# ledpar56.net
KiCad netlist of a schematic drawn in EAGLE
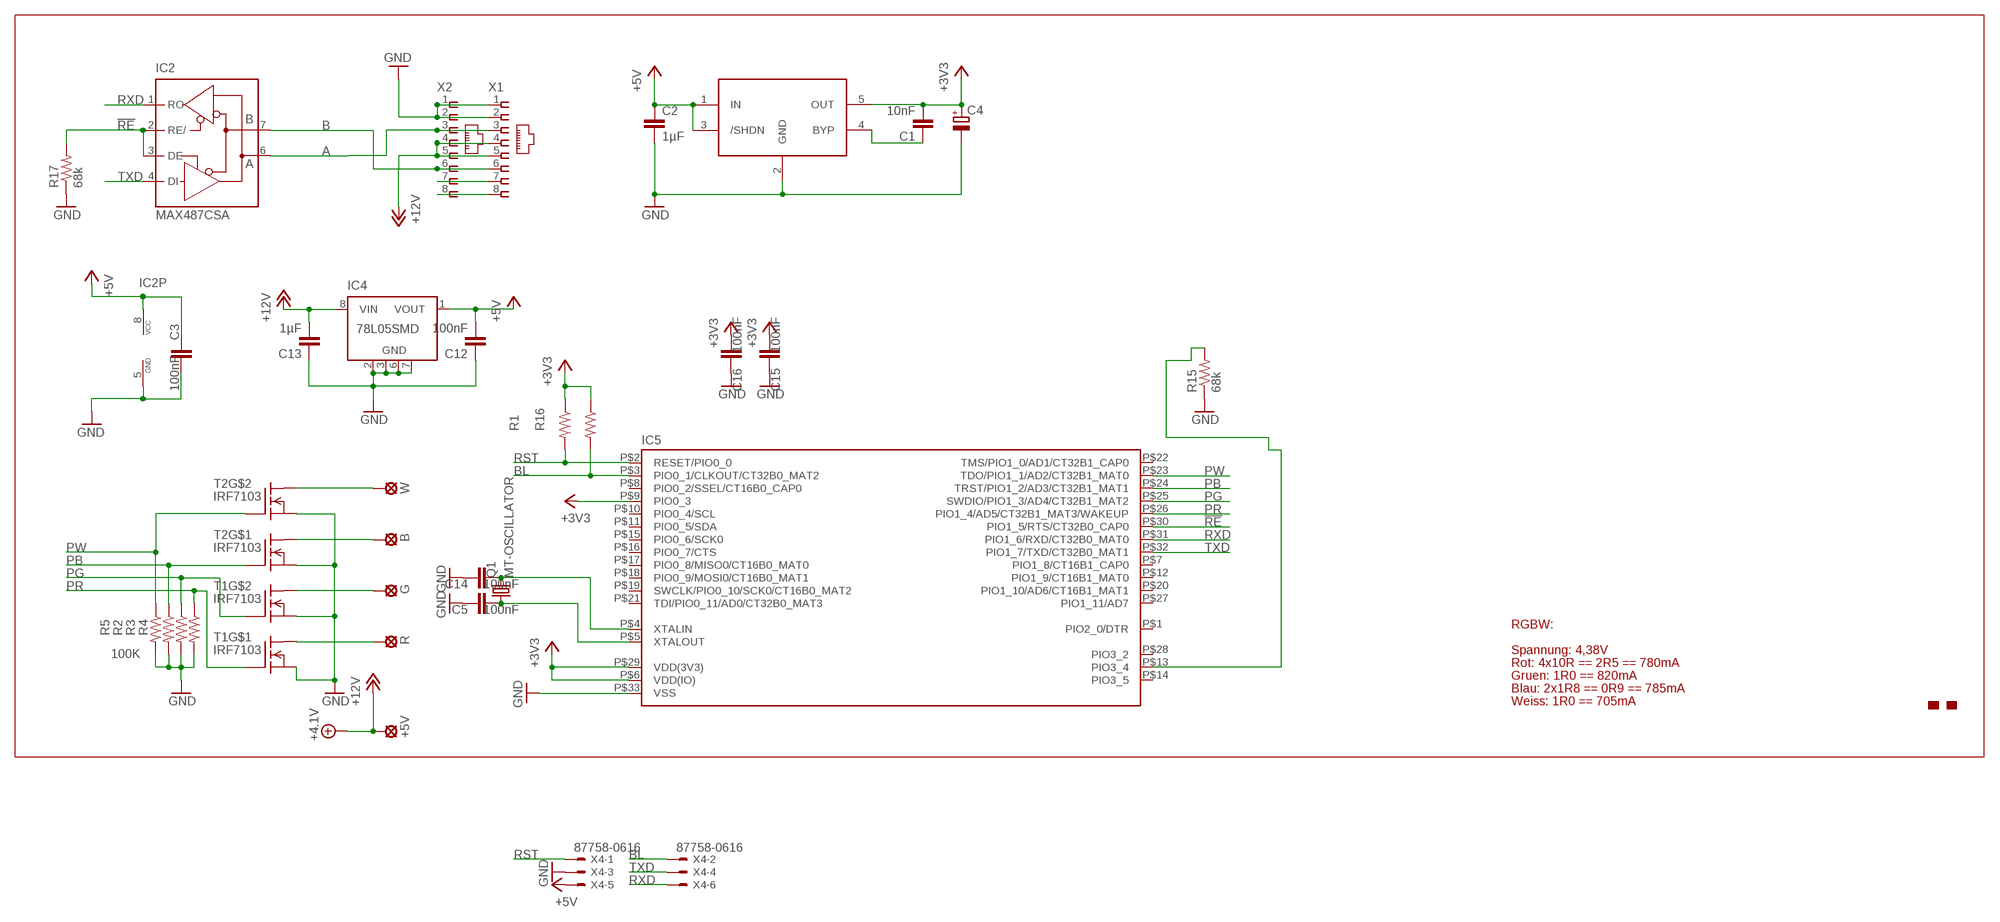
[diagram p0: schematic, sheet 1]

(export (version "E")
  (design (tool "Eeschema 10.0.6"))
  (components
    (comp (ref "+5V")
      (value "SE14")
      (footprint "eagle-import:SE14")
      (libsource (lib "eagle-import") (part "SE14"))
    )
    (comp (ref "B")
      (value "SE14")
      (footprint "eagle-import:SE14")
      (libsource (lib "eagle-import") (part "SE14"))
    )
    (comp (ref "C1")
      (value "10nF")
      (footprint "eagle-import:C0402")
      (libsource (lib "eagle-import") (part "C-EUC0402"))
    )
    (comp (ref "C2")
      (value "1µF")
      (footprint "eagle-import:0805")
      (libsource (lib "eagle-import") (part "SparkFun-Capacitors_CAP0805"))
    )
    (comp (ref "C3")
      (value "100nF")
      (footprint "eagle-import:0402-CAP")
      (libsource (lib "eagle-import") (part "CAP0402-CAP"))
    )
    (comp (ref "C4")
      (value "CPOL-EUSMCA")
      (footprint "eagle-import:SMC_A")
      (libsource (lib "eagle-import") (part "CPOL-EUSMCA"))
    )
    (comp (ref "C5")
      (value "100nF")
      (footprint "eagle-import:0402-CAP")
      (libsource (lib "eagle-import") (part "CAP0402-CAP"))
    )
    (comp (ref "C12")
      (value "100nF")
      (footprint "eagle-import:0402-CAP")
      (libsource (lib "eagle-import") (part "CAP0402-CAP"))
    )
    (comp (ref "C13")
      (value "1µF")
      (footprint "eagle-import:0805")
      (libsource (lib "eagle-import") (part "CAP0805"))
    )
    (comp (ref "C14")
      (value "100nF")
      (footprint "eagle-import:0402-CAP")
      (libsource (lib "eagle-import") (part "CAP0402-CAP"))
    )
    (comp (ref "C15")
      (value "100nF")
      (footprint "eagle-import:0402-CAP")
      (libsource (lib "eagle-import") (part "CAP0402-CAP"))
    )
    (comp (ref "C16")
      (value "100nF")
      (footprint "eagle-import:0402-CAP")
      (libsource (lib "eagle-import") (part "CAP0402-CAP"))
    )
    (comp (ref "G")
      (value "SE14")
      (footprint "eagle-import:SE14")
      (libsource (lib "eagle-import") (part "SE14"))
    )
    (comp (ref "IC1")
      (value "LT1761")
      (footprint "eagle-import:SOT23-5L")
      (libsource (lib "eagle-import") (part "LT1761"))
    )
    (comp (ref "IC2")
      (value "MAX487CSA")
      (footprint "eagle-import:SO08")
      (fields (field (name "MF") "MAXIM") (field (name "MPN") "MAX481CSA"))
      (libsource (lib "eagle-import") (part "MAX481CSA"))
    )
    (comp (ref "IC4")
      (value "78L05SMD")
      (footprint "eagle-import:SO08")
      (libsource (lib "eagle-import") (part "78LSMD05"))
    )
    (comp (ref "IC5")
      (value "LPC1113/4_QFN")
      (footprint "eagle-import:HVQFN33-7X7")
      (fields (field (name "MANF") "NXP"))
      (libsource (lib "eagle-import") (part "LPC1113/4_QFN"))
    )
    (comp (ref "Q1")
      (value "MT-OSCILLATOR")
      (footprint "eagle-import:MT")
      (libsource (lib "eagle-import") (part "MT-OSCILLATOR"))
    )
    (comp (ref "R")
      (value "SE14")
      (footprint "eagle-import:SE14")
      (libsource (lib "eagle-import") (part "SE14"))
    )
    (comp (ref "R1")
      (value "100K")
      (footprint "eagle-import:0402-RES")
      (libsource (lib "eagle-import") (part "RESISTOR0402-RES"))
    )
    (comp (ref "R2")
      (value "100K")
      (footprint "eagle-import:0402-RES")
      (libsource (lib "eagle-import") (part "RESISTOR0402-RES"))
    )
    (comp (ref "R3")
      (value "100K")
      (footprint "eagle-import:0402-RES")
      (libsource (lib "eagle-import") (part "RESISTOR0402-RES"))
    )
    (comp (ref "R4")
      (value "100K")
      (footprint "eagle-import:0402-RES")
      (libsource (lib "eagle-import") (part "RESISTOR0402-RES"))
    )
    (comp (ref "R5")
      (value "100K")
      (footprint "eagle-import:0402-RES")
      (libsource (lib "eagle-import") (part "RESISTOR0402-RES"))
    )
    (comp (ref "R15")
      (value "68k")
      (footprint "eagle-import:0402-RES")
      (libsource (lib "eagle-import") (part "RESISTOR0402-RES"))
    )
    (comp (ref "R16")
      (value "100K")
      (footprint "eagle-import:0402-RES")
      (libsource (lib "eagle-import") (part "RESISTOR0402-RES"))
    )
    (comp (ref "R17")
      (value "68k")
      (footprint "eagle-import:0402-RES")
      (libsource (lib "eagle-import") (part "RESISTOR0402-RES"))
    )
    (comp (ref "T1")
      (value "IRF7103")
      (footprint "eagle-import:SO-8")
      (libsource (lib "eagle-import") (part "IRF7103"))
    )
    (comp (ref "T2")
      (value "IRF7103")
      (footprint "eagle-import:SO-8")
      (libsource (lib "eagle-import") (part "IRF7103"))
    )
    (comp (ref "U$1")
      (value "MAKE-DD_LOGO'PROMPT'")
      (footprint "eagle-import:MAKE-DD_LOGO_PROMPT")
      (libsource (lib "eagle-import") (part "MAKE-DD_LOGO'PROMPT'"))
    )
    (comp (ref "W")
      (value "SE14")
      (footprint "eagle-import:SE14")
      (libsource (lib "eagle-import") (part "SE14"))
    )
    (comp (ref "X1")
      (value "RJ45-8L-B")
      (footprint "eagle-import:RJ45-NO-SHIELD")
      (fields (field (name "MF") "TYCO ELECTRONICS"))
      (libsource (lib "eagle-import") (part "RJ45-8L-B"))
    )
    (comp (ref "X2")
      (value "RJ45-8L-B")
      (footprint "eagle-import:RJ45-NO-SHIELD")
      (fields (field (name "MF") "TYCO ELECTRONICS"))
      (libsource (lib "eagle-import") (part "RJ45-8L-B"))
    )
    (comp (ref "X4")
      (value "87758-0616")
      (footprint "eagle-import:87758-0616")
      (libsource (lib "eagle-import") (part "87758-0616"))
    )
  )
  (nets
    (net (code "1") (name "+3V3") (class "Default")
      (node (ref "C1") (pin "2") (pinfunction "2_2") (pintype "passive"))
      (node (ref "C15") (pin "2") (pinfunction "2_2") (pintype "passive"))
      (node (ref "C16") (pin "2") (pinfunction "2_2") (pintype "passive"))
      (node (ref "C4") (pin "+") (pinfunction "+_+") (pintype "passive"))
      (node (ref "IC1") (pin "5") (pinfunction "OUT_5") (pintype "bidirectional"))
      (node (ref "IC5") (pin "P$29") (pinfunction "VDD(3V3)_P$29") (pintype "power_in"))
      (node (ref "IC5") (pin "P$6") (pinfunction "VDD(IO)_P$6") (pintype "power_in"))
      (node (ref "IC5") (pin "P$9") (pinfunction "PIO0_3_P$9") (pintype "bidirectional"))
      (node (ref "R1") (pin "1") (pinfunction "1_1") (pintype "passive"))
      (node (ref "R16") (pin "1") (pinfunction "1_1") (pintype "passive"))
    )
    (net (code "2") (name "+5V") (class "Default")
      (node (ref "C12") (pin "2") (pinfunction "2_2") (pintype "passive"))
      (node (ref "C2") (pin "1") (pinfunction "1_1") (pintype "passive"))
      (node (ref "C3") (pin "1") (pinfunction "1_1") (pintype "passive"))
      (node (ref "IC1") (pin "1") (pinfunction "IN_1") (pintype "bidirectional"))
      (node (ref "IC1") (pin "3") (pinfunction "/SHDN_3") (pintype "bidirectional"))
      (node (ref "IC2") (pin "8") (pinfunction "VCC_8") (pintype "power_in"))
      (node (ref "IC4") (pin "1") (pinfunction "VOUT_1") (pintype "output"))
      (node (ref "X4") (pin "5") (pinfunction "S_5") (pintype "passive"))
    )
    (net (code "3") (name "+12V") (class "Default")
      (node (ref "+5V") (pin "MP") (pinfunction "MP_MP") (pintype "passive"))
      (node (ref "C13") (pin "2") (pinfunction "2_2") (pintype "passive"))
      (node (ref "IC4") (pin "8") (pinfunction "VIN_8") (pintype "passive"))
      (node (ref "X1") (pin "4") (pinfunction "4_4") (pintype "passive"))
      (node (ref "X1") (pin "5") (pinfunction "5_5") (pintype "passive"))
      (node (ref "X2") (pin "4") (pinfunction "4_4") (pintype "passive"))
      (node (ref "X2") (pin "5") (pinfunction "5_5") (pintype "passive"))
    )
    (net (code "4") (name "/A") (class "Default")
      (node (ref "IC2") (pin "6") (pinfunction "A_6") (pintype "passive"))
      (node (ref "X1") (pin "3") (pinfunction "3_3") (pintype "passive"))
      (node (ref "X2") (pin "3") (pinfunction "3_3") (pintype "passive"))
    )
    (net (code "5") (name "/B") (class "Default")
      (node (ref "IC2") (pin "7") (pinfunction "B_7") (pintype "passive"))
      (node (ref "X1") (pin "6") (pinfunction "6_6") (pintype "passive"))
      (node (ref "X2") (pin "6") (pinfunction "6_6") (pintype "passive"))
    )
    (net (code "6") (name "/BL") (class "Default")
      (node (ref "IC5") (pin "P$3") (pinfunction "PIO0_1/CLKOUT/CT32B0_MAT2_P$3") (pintype "bidirectional"))
      (node (ref "R16") (pin "2") (pinfunction "2_2") (pintype "passive"))
      (node (ref "X4") (pin "2") (pinfunction "S_2") (pintype "passive"))
    )
    (net (code "7") (name "/PB") (class "Default")
      (node (ref "IC5") (pin "P$24") (pinfunction "TRST/PIO1_2/AD3/CT32B1_MAT1_P$24") (pintype "bidirectional"))
      (node (ref "R2") (pin "1") (pinfunction "1_1") (pintype "passive"))
      (node (ref "T2") (pin "2") (pinfunction "G_2") (pintype "passive"))
    )
    (net (code "8") (name "/PG") (class "Default")
      (node (ref "IC5") (pin "P$25") (pinfunction "SWDIO/PIO1_3/AD4/CT32B1_MAT2_P$25") (pintype "bidirectional"))
      (node (ref "R3") (pin "1") (pinfunction "1_1") (pintype "passive"))
      (node (ref "T1") (pin "4") (pinfunction "G_4") (pintype "passive"))
    )
    (net (code "9") (name "/PR") (class "Default")
      (node (ref "IC5") (pin "P$26") (pinfunction "PIO1_4/AD5/CT32B1_MAT3/WAKEUP_P$26") (pintype "bidirectional"))
      (node (ref "R4") (pin "1") (pinfunction "1_1") (pintype "passive"))
      (node (ref "T1") (pin "2") (pinfunction "G_2") (pintype "passive"))
    )
    (net (code "10") (name "/PW") (class "Default")
      (node (ref "IC5") (pin "P$23") (pinfunction "TDO/PIO1_1/AD2/CT32B1_MAT0_P$23") (pintype "bidirectional"))
      (node (ref "R5") (pin "1") (pinfunction "1_1") (pintype "passive"))
      (node (ref "T2") (pin "4") (pinfunction "G_4") (pintype "passive"))
    )
    (net (code "11") (name "/RST") (class "Default")
      (node (ref "IC5") (pin "P$2") (pinfunction "RESET/PIO0_0_P$2") (pintype "bidirectional"))
      (node (ref "R1") (pin "2") (pinfunction "2_2") (pintype "passive"))
      (node (ref "X4") (pin "1") (pinfunction "S_1") (pintype "passive"))
    )
    (net (code "12") (name "/RXD") (class "Default")
      (node (ref "IC2") (pin "1") (pinfunction "RO_1") (pintype "output"))
      (node (ref "IC5") (pin "P$31") (pinfunction "PIO1_6/RXD/CT32B0_MAT0_P$31") (pintype "bidirectional"))
      (node (ref "X4") (pin "6") (pinfunction "S_6") (pintype "passive"))
    )
    (net (code "13") (name "/TXD") (class "Default")
      (node (ref "IC2") (pin "4") (pinfunction "DI_4") (pintype "input"))
      (node (ref "IC5") (pin "P$32") (pinfunction "PIO1_7/TXD/CT32B0_MAT1_P$32") (pintype "bidirectional"))
      (node (ref "X4") (pin "4") (pinfunction "S_4") (pintype "passive"))
    )
    (net (code "14") (name "/~{RE}") (class "Default")
      (node (ref "IC2") (pin "2") (pinfunction "RE/_2") (pintype "input"))
      (node (ref "IC2") (pin "3") (pinfunction "DE_3") (pintype "input"))
      (node (ref "IC5") (pin "P$30") (pinfunction "PIO1_5/RTS/CT32B0_CAP0_P$30") (pintype "bidirectional"))
      (node (ref "R17") (pin "2") (pinfunction "2_2") (pintype "passive"))
    )
    (net (code "15") (name "GND") (class "Default")
      (node (ref "C12") (pin "1") (pinfunction "1_1") (pintype "passive"))
      (node (ref "C13") (pin "1") (pinfunction "1_1") (pintype "passive"))
      (node (ref "C14") (pin "1") (pinfunction "1_1") (pintype "passive"))
      (node (ref "C15") (pin "1") (pinfunction "1_1") (pintype "passive"))
      (node (ref "C16") (pin "1") (pinfunction "1_1") (pintype "passive"))
      (node (ref "C2") (pin "2") (pinfunction "2_2") (pintype "passive"))
      (node (ref "C3") (pin "2") (pinfunction "2_2") (pintype "passive"))
      (node (ref "C4") (pin "-") (pinfunction "-_-") (pintype "passive"))
      (node (ref "C5") (pin "1") (pinfunction "1_1") (pintype "passive"))
      (node (ref "IC1") (pin "2") (pinfunction "GND_2") (pintype "bidirectional"))
      (node (ref "IC2") (pin "5") (pinfunction "GND_5") (pintype "power_in"))
      (node (ref "IC4") (pin "2") (pinfunction "GND_2") (pintype "power_in"))
      (node (ref "IC4") (pin "3") (pinfunction "GND_3") (pintype "power_in"))
      (node (ref "IC4") (pin "6") (pinfunction "GND_6") (pintype "power_in"))
      (node (ref "IC4") (pin "7") (pinfunction "GND_7") (pintype "power_in"))
      (node (ref "IC5") (pin "P$33") (pinfunction "VSS_P$33") (pintype "power_in"))
      (node (ref "R15") (pin "1") (pinfunction "1_1") (pintype "passive"))
      (node (ref "R17") (pin "1") (pinfunction "1_1") (pintype "passive"))
      (node (ref "R2") (pin "2") (pinfunction "2_2") (pintype "passive"))
      (node (ref "R3") (pin "2") (pinfunction "2_2") (pintype "passive"))
      (node (ref "R4") (pin "2") (pinfunction "2_2") (pintype "passive"))
      (node (ref "R5") (pin "2") (pinfunction "2_2") (pintype "passive"))
      (node (ref "T1") (pin "1") (pinfunction "S_1") (pintype "passive"))
      (node (ref "T1") (pin "3") (pinfunction "S_3") (pintype "passive"))
      (node (ref "T2") (pin "1") (pinfunction "S_1") (pintype "passive"))
      (node (ref "T2") (pin "3") (pinfunction "S_3") (pintype "passive"))
      (node (ref "X1") (pin "1") (pinfunction "1_1") (pintype "passive"))
      (node (ref "X1") (pin "2") (pinfunction "2_2") (pintype "passive"))
      (node (ref "X2") (pin "1") (pinfunction "1_1") (pintype "passive"))
      (node (ref "X2") (pin "2") (pinfunction "2_2") (pintype "passive"))
      (node (ref "X4") (pin "3") (pinfunction "S_3") (pintype "passive"))
    )
    (net (code "16") (name "Net-(IC1-BYP)") (class "Default")
      (node (ref "C1") (pin "1") (pinfunction "1_1") (pintype "passive"))
      (node (ref "IC1") (pin "4") (pinfunction "BYP_4") (pintype "bidirectional"))
    )
    (net (code "17") (name "Net-(IC5-PIO3_4)") (class "Default")
      (node (ref "IC5") (pin "P$13") (pinfunction "PIO3_4_P$13") (pintype "bidirectional"))
      (node (ref "R15") (pin "2") (pinfunction "2_2") (pintype "passive"))
    )
    (net (code "18") (name "Net-(IC5-XTALIN)") (class "Default")
      (node (ref "C14") (pin "2") (pinfunction "2_2") (pintype "passive"))
      (node (ref "IC5") (pin "P$4") (pinfunction "XTALIN_P$4") (pintype "input"))
      (node (ref "Q1") (pin "3") (pinfunction "2_3") (pintype "passive"))
    )
    (net (code "19") (name "Net-(IC5-XTALOUT)") (class "Default")
      (node (ref "C5") (pin "2") (pinfunction "2_2") (pintype "passive"))
      (node (ref "IC5") (pin "P$5") (pinfunction "XTALOUT_P$5") (pintype "output"))
      (node (ref "Q1") (pin "1") (pinfunction "1_1") (pintype "passive"))
    )
    (net (code "20") (name "Net-(T1A-D1)") (class "Default")
      (node (ref "R") (pin "MP") (pinfunction "MP_MP") (pintype "passive"))
      (node (ref "T1") (pin "8") (pinfunction "D1_8") (pintype "passive"))
    )
    (net (code "21") (name "Net-(T1B-D1)") (class "Default")
      (node (ref "G") (pin "MP") (pinfunction "MP_MP") (pintype "passive"))
      (node (ref "T1") (pin "5") (pinfunction "D1_5") (pintype "passive"))
    )
    (net (code "22") (name "Net-(T2A-D1)") (class "Default")
      (node (ref "B") (pin "MP") (pinfunction "MP_MP") (pintype "passive"))
      (node (ref "T2") (pin "8") (pinfunction "D1_8") (pintype "passive"))
    )
    (net (code "23") (name "Net-(T2B-D1)") (class "Default")
      (node (ref "T2") (pin "5") (pinfunction "D1_5") (pintype "passive"))
      (node (ref "W") (pin "MP") (pinfunction "MP_MP") (pintype "passive"))
    )
    (net (code "24") (name "Net-(X1-Pad7)") (class "Default")
      (node (ref "X1") (pin "7") (pinfunction "7_7") (pintype "passive"))
      (node (ref "X2") (pin "7") (pinfunction "7_7") (pintype "passive"))
    )
    (net (code "25") (name "Net-(X1-Pad8)") (class "Default")
      (node (ref "X1") (pin "8") (pinfunction "8_8") (pintype "passive"))
      (node (ref "X2") (pin "8") (pinfunction "8_8") (pintype "passive"))
    )
    (net (code "26") (name "unconnected-(IC5-PIO0_2{slash}SSEL{slash}CT16B0_CAP0-PadP$8)") (class "Default")
      (node (ref "IC5") (pin "P$8") (pinfunction "PIO0_2/SSEL/CT16B0_CAP0_P$8") (pintype "bidirectional"))
    )
    (net (code "27") (name "unconnected-(IC5-PIO0_4{slash}SCL-PadP$10)") (class "Default")
      (node (ref "IC5") (pin "P$10") (pinfunction "PIO0_4/SCL_P$10") (pintype "bidirectional"))
    )
    (net (code "28") (name "unconnected-(IC5-PIO0_5{slash}SDA-PadP$11)") (class "Default")
      (node (ref "IC5") (pin "P$11") (pinfunction "PIO0_5/SDA_P$11") (pintype "bidirectional"))
    )
    (net (code "29") (name "unconnected-(IC5-PIO0_6{slash}SCK0-PadP$15)") (class "Default")
      (node (ref "IC5") (pin "P$15") (pinfunction "PIO0_6/SCK0_P$15") (pintype "bidirectional"))
    )
    (net (code "30") (name "unconnected-(IC5-PIO0_7{slash}CTS-PadP$16)") (class "Default")
      (node (ref "IC5") (pin "P$16") (pinfunction "PIO0_7/CTS_P$16") (pintype "bidirectional"))
    )
    (net (code "31") (name "unconnected-(IC5-PIO0_8{slash}MISO0{slash}CT16B0_MAT0-PadP$17)") (class "Default")
      (node (ref "IC5") (pin "P$17") (pinfunction "PIO0_8/MISO0/CT16B0_MAT0_P$17") (pintype "bidirectional"))
    )
    (net (code "32") (name "unconnected-(IC5-PIO0_9{slash}MOSI0{slash}CT16B0_MAT1-PadP$18)") (class "Default")
      (node (ref "IC5") (pin "P$18") (pinfunction "PIO0_9/MOSI0/CT16B0_MAT1_P$18") (pintype "bidirectional"))
    )
    (net (code "33") (name "unconnected-(IC5-PIO1_8{slash}CT16B1_CAP0-PadP$7)") (class "Default")
      (node (ref "IC5") (pin "P$7") (pinfunction "PIO1_8/CT16B1_CAP0_P$7") (pintype "bidirectional"))
    )
    (net (code "34") (name "unconnected-(IC5-PIO1_9{slash}CT16B1_MAT0-PadP$12)") (class "Default")
      (node (ref "IC5") (pin "P$12") (pinfunction "PIO1_9/CT16B1_MAT0_P$12") (pintype "bidirectional"))
    )
    (net (code "35") (name "unconnected-(IC5-PIO1_10{slash}AD6{slash}CT16B1_MAT1-PadP$20)") (class "Default")
      (node (ref "IC5") (pin "P$20") (pinfunction "PIO1_10/AD6/CT16B1_MAT1_P$20") (pintype "bidirectional"))
    )
    (net (code "36") (name "unconnected-(IC5-PIO1_11{slash}AD7-PadP$27)") (class "Default")
      (node (ref "IC5") (pin "P$27") (pinfunction "PIO1_11/AD7_P$27") (pintype "bidirectional"))
    )
    (net (code "37") (name "unconnected-(IC5-PIO2_0{slash}DTR-PadP$1)") (class "Default")
      (node (ref "IC5") (pin "P$1") (pinfunction "PIO2_0/DTR_P$1") (pintype "bidirectional"))
    )
    (net (code "38") (name "unconnected-(IC5-PIO3_2-PadP$28)") (class "Default")
      (node (ref "IC5") (pin "P$28") (pinfunction "PIO3_2_P$28") (pintype "bidirectional"))
    )
    (net (code "39") (name "unconnected-(IC5-PIO3_5-PadP$14)") (class "Default")
      (node (ref "IC5") (pin "P$14") (pinfunction "PIO3_5_P$14") (pintype "bidirectional"))
    )
    (net (code "40") (name "unconnected-(IC5-SWCLK{slash}PIO0_10{slash}SCK0{slash}CT16B0_MAT2-PadP$19)") (class "Default")
      (node (ref "IC5") (pin "P$19") (pinfunction "SWCLK/PIO0_10/SCK0/CT16B0_MAT2_P$19") (pintype "bidirectional"))
    )
    (net (code "41") (name "unconnected-(IC5-TDI{slash}PIO0_11{slash}AD0{slash}CT32B0_MAT3-PadP$21)") (class "Default")
      (node (ref "IC5") (pin "P$21") (pinfunction "TDI/PIO0_11/AD0/CT32B0_MAT3_P$21") (pintype "bidirectional"))
    )
    (net (code "42") (name "unconnected-(IC5-TMS{slash}PIO1_0{slash}AD1{slash}CT32B1_CAP0-PadP$22)") (class "Default")
      (node (ref "IC5") (pin "P$22") (pinfunction "TMS/PIO1_0/AD1/CT32B1_CAP0_P$22") (pintype "bidirectional"))
    )
    (net (code "43") (name "unconnected-(T1A-D-Pad7)") (class "Default")
      (node (ref "T1") (pin "7") (pinfunction "D_7") (pintype "passive"))
    )
    (net (code "44") (name "unconnected-(T1B-D-Pad6)") (class "Default")
      (node (ref "T1") (pin "6") (pinfunction "D_6") (pintype "passive"))
    )
    (net (code "45") (name "unconnected-(T2A-D-Pad7)") (class "Default")
      (node (ref "T2") (pin "7") (pinfunction "D_7") (pintype "passive"))
    )
    (net (code "46") (name "unconnected-(T2B-D-Pad6)") (class "Default")
      (node (ref "T2") (pin "6") (pinfunction "D_6") (pintype "passive"))
    )
  )
)
